# Sheet2.net
KiCad netlist of a schematic drawn in Altium Designer
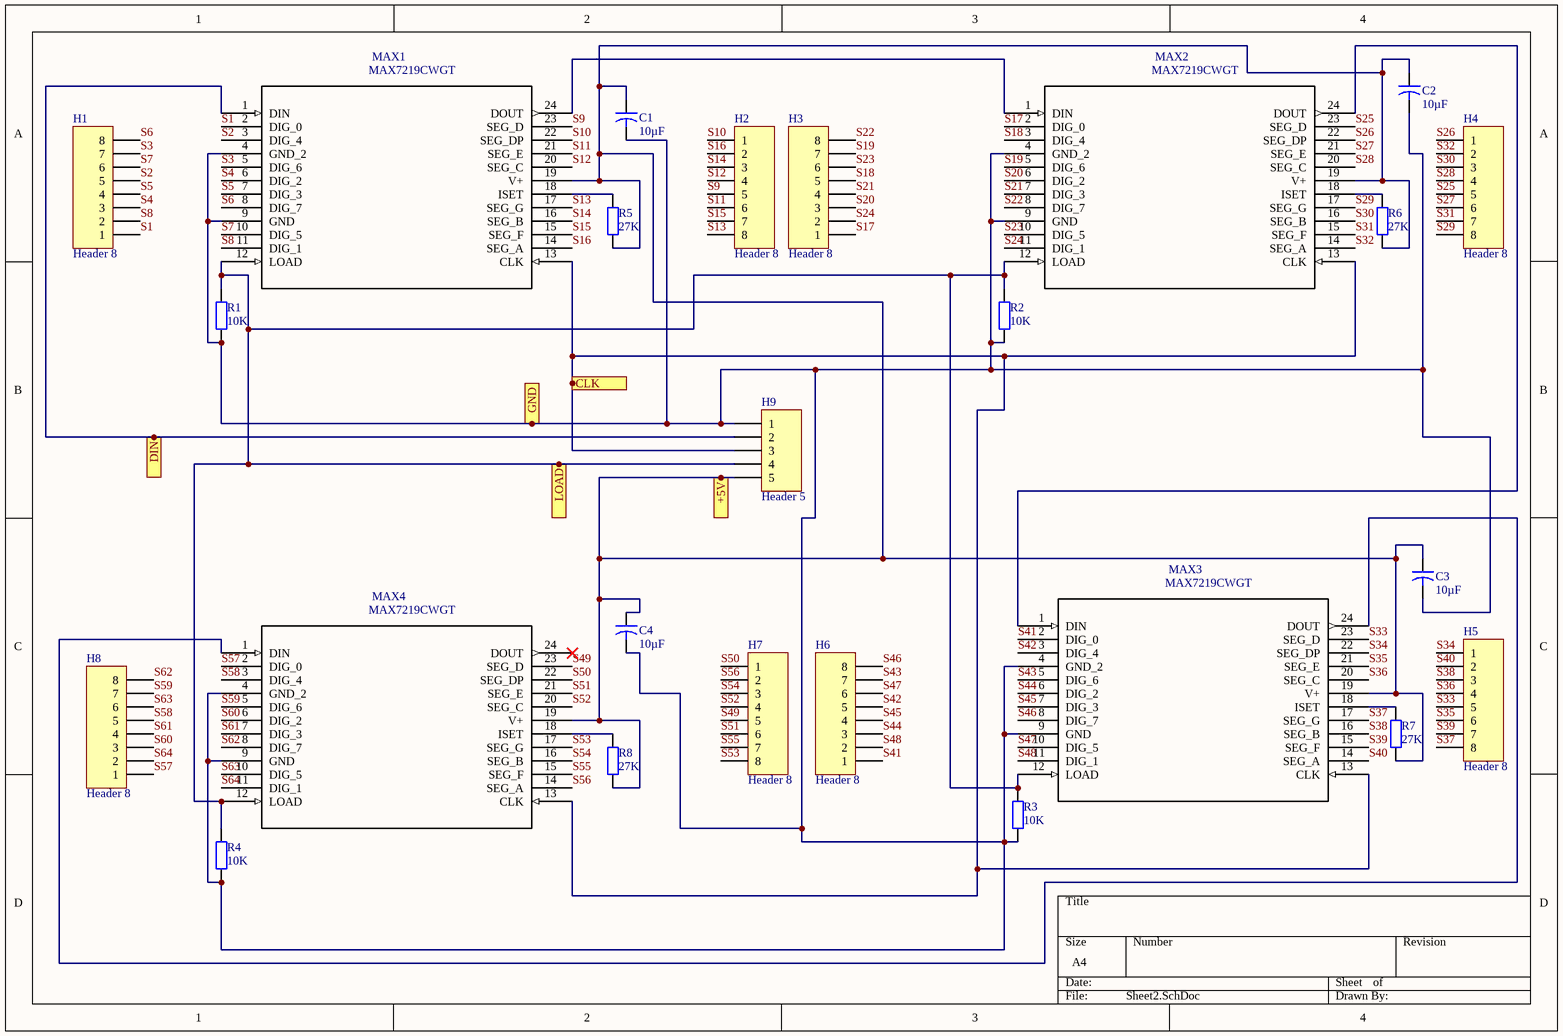
[diagram p0: Sheet2.SchDoc]

(export (version "E")
  (design (tool "Eeschema 10.0.6"))
  (components
    (comp (ref "C1")
      (value "10µF")
      (footprint "CAPR5-4X5")
      (description "Capacitor")
      (fields (field (name "Comment") "Cap2") (field (name "PUBLISHER") "Altium Limited"))
      (libsource (lib "PCB_Project_1_1") (part "Cap2"))
    )
    (comp (ref "C2")
      (value "10µF")
      (footprint "CAPR5-4X5")
      (description "Capacitor")
      (fields (field (name "Comment") "Cap2") (field (name "PUBLISHER") "Altium Limited"))
      (libsource (lib "PCB_Project_1_1") (part "Cap2"))
    )
    (comp (ref "C3")
      (value "10µF")
      (footprint "CAPR5-4X5")
      (description "Capacitor")
      (fields (field (name "Comment") "Cap2") (field (name "PUBLISHER") "Altium Limited"))
      (libsource (lib "PCB_Project_1_1") (part "Cap2"))
    )
    (comp (ref "C4")
      (value "10µF")
      (footprint "CAPR5-4X5")
      (description "Capacitor")
      (fields (field (name "Comment") "Cap2") (field (name "PUBLISHER") "Altium Limited"))
      (libsource (lib "PCB_Project_1_1") (part "Cap2"))
    )
    (comp (ref "H1")
      (value "Header 8")
      (footprint "HDR1X8")
      (description "Header, 8-Pin")
      (fields (field (name "PUBLISHER") "Altium Limited"))
      (libsource (lib "Miscellaneous Connectors") (part "Header 8"))
    )
    (comp (ref "H2")
      (value "Header 8")
      (footprint "HDR1X8")
      (description "Header, 8-Pin")
      (fields (field (name "PUBLISHER") "Altium Limited"))
      (libsource (lib "") (part "Header 8_1"))
    )
    (comp (ref "H3")
      (value "Header 8")
      (footprint "HDR1X8")
      (description "Header, 8-Pin")
      (fields (field (name "PUBLISHER") "Altium Limited"))
      (libsource (lib "Miscellaneous Connectors") (part "Header 8"))
    )
    (comp (ref "H4")
      (value "Header 8")
      (footprint "HDR1X8")
      (description "Header, 8-Pin")
      (fields (field (name "PUBLISHER") "Altium Limited"))
      (libsource (lib "") (part "Header 8_1"))
    )
    (comp (ref "H5")
      (value "Header 8")
      (footprint "HDR1X8")
      (description "Header, 8-Pin")
      (fields (field (name "PUBLISHER") "Altium Limited"))
      (libsource (lib "") (part "Header 8_1"))
    )
    (comp (ref "H6")
      (value "Header 8")
      (footprint "HDR1X8")
      (description "Header, 8-Pin")
      (fields (field (name "PUBLISHER") "Altium Limited"))
      (libsource (lib "Miscellaneous Connectors") (part "Header 8"))
    )
    (comp (ref "H7")
      (value "Header 8")
      (footprint "HDR1X8")
      (description "Header, 8-Pin")
      (fields (field (name "PUBLISHER") "Altium Limited"))
      (libsource (lib "") (part "Header 8_1"))
    )
    (comp (ref "H8")
      (value "Header 8")
      (footprint "HDR1X8")
      (description "Header, 8-Pin")
      (fields (field (name "PUBLISHER") "Altium Limited"))
      (libsource (lib "Miscellaneous Connectors") (part "Header 8"))
    )
    (comp (ref "H9")
      (value "Header 5")
      (footprint "HDR1X5")
      (description "Header, 5-Pin")
      (fields (field (name "PUBLISHER") "Altium Limited"))
      (libsource (lib "Miscellaneous Connectors") (part "Header 5"))
    )
    (comp (ref "MAX1")
      (value "MAX7219CWGT")
      (footprint "*21-0042B_24")
      (libsource (lib "MAX7219CWGT") (part "MAX7219CWGT"))
    )
    (comp (ref "MAX2")
      (value "MAX7219CWGT")
      (footprint "*21-0042B_24")
      (libsource (lib "MAX7219CWGT") (part "MAX7219CWGT"))
    )
    (comp (ref "MAX3")
      (value "MAX7219CWGT")
      (footprint "*21-0042B_24")
      (libsource (lib "MAX7219CWGT") (part "MAX7219CWGT"))
    )
    (comp (ref "MAX4")
      (value "MAX7219CWGT")
      (footprint "*21-0042B_24")
      (libsource (lib "MAX7219CWGT") (part "MAX7219CWGT"))
    )
    (comp (ref "R1")
      (value "10K")
      (footprint "AXIAL-0.4")
      (description "Resistor")
      (fields (field (name "Comment") "Res2") (field (name "PUBLISHER") "Altium Limited"))
      (libsource (lib "PCB_Project_1_1") (part "Res2_1"))
    )
    (comp (ref "R2")
      (value "10K")
      (footprint "AXIAL-0.4")
      (description "Resistor")
      (fields (field (name "Comment") "Res2") (field (name "PUBLISHER") "Altium Limited"))
      (libsource (lib "PCB_Project_1_1") (part "Res2_1"))
    )
    (comp (ref "R3")
      (value "10K")
      (footprint "AXIAL-0.4")
      (description "Resistor")
      (fields (field (name "Comment") "Res2") (field (name "PUBLISHER") "Altium Limited"))
      (libsource (lib "PCB_Project_1_1") (part "Res2_1"))
    )
    (comp (ref "R4")
      (value "10K")
      (footprint "AXIAL-0.4")
      (description "Resistor")
      (fields (field (name "Comment") "Res2") (field (name "PUBLISHER") "Altium Limited"))
      (libsource (lib "PCB_Project_1_1") (part "Res2_1"))
    )
    (comp (ref "R5")
      (value "27K")
      (footprint "AXIAL-0.4")
      (description "Resistor")
      (fields (field (name "Comment") "Res2") (field (name "PUBLISHER") "Altium Limited"))
      (libsource (lib "PCB_Project_1_1") (part "Res2"))
    )
    (comp (ref "R6")
      (value "27K")
      (footprint "AXIAL-0.4")
      (description "Resistor")
      (fields (field (name "Comment") "Res2") (field (name "PUBLISHER") "Altium Limited"))
      (libsource (lib "PCB_Project_1_1") (part "Res2"))
    )
    (comp (ref "R7")
      (value "27K")
      (footprint "AXIAL-0.4")
      (description "Resistor")
      (fields (field (name "Comment") "Res2") (field (name "PUBLISHER") "Altium Limited"))
      (libsource (lib "PCB_Project_1_1") (part "Res2"))
    )
    (comp (ref "R8")
      (value "27K")
      (footprint "AXIAL-0.4")
      (description "Resistor")
      (fields (field (name "Comment") "Res2") (field (name "PUBLISHER") "Altium Limited"))
      (libsource (lib "PCB_Project_1_1") (part "Res2"))
    )
  )
  (nets
    (net (code "1") (name "/+5V") (class "Default")
      (node (ref "C1") (pin "1") (pinfunction "1_1") (pintype "passive"))
      (node (ref "C2") (pin "1") (pinfunction "1_1") (pintype "passive"))
      (node (ref "C3") (pin "1") (pinfunction "1_1") (pintype "passive"))
      (node (ref "C4") (pin "1") (pinfunction "1_1") (pintype "passive"))
      (node (ref "H9") (pin "5") (pinfunction "5_5") (pintype "passive"))
      (node (ref "MAX1") (pin "19") (pinfunction "V+_19") (pintype "power_in"))
      (node (ref "MAX2") (pin "19") (pinfunction "V+_19") (pintype "power_in"))
      (node (ref "MAX3") (pin "19") (pinfunction "V+_19") (pintype "power_in"))
      (node (ref "MAX4") (pin "19") (pinfunction "V+_19") (pintype "power_in"))
      (node (ref "R5") (pin "1") (pinfunction "1_1") (pintype "passive"))
      (node (ref "R6") (pin "1") (pinfunction "1_1") (pintype "passive"))
      (node (ref "R7") (pin "1") (pinfunction "1_1") (pintype "passive"))
      (node (ref "R8") (pin "1") (pinfunction "1_1") (pintype "passive"))
    )
    (net (code "2") (name "/CLK") (class "Default")
      (node (ref "H9") (pin "3") (pinfunction "3_3") (pintype "passive"))
      (node (ref "MAX1") (pin "13") (pinfunction "CLK_13") (pintype "input"))
      (node (ref "MAX2") (pin "13") (pinfunction "CLK_13") (pintype "input"))
      (node (ref "MAX3") (pin "13") (pinfunction "CLK_13") (pintype "input"))
      (node (ref "MAX4") (pin "13") (pinfunction "CLK_13") (pintype "input"))
    )
    (net (code "3") (name "/DIN") (class "Default")
      (node (ref "H9") (pin "2") (pinfunction "2_2") (pintype "passive"))
      (node (ref "MAX1") (pin "1") (pinfunction "DIN_1") (pintype "input"))
    )
    (net (code "4") (name "/GND") (class "Default")
      (node (ref "C1") (pin "2") (pinfunction "2_2") (pintype "passive"))
      (node (ref "C2") (pin "2") (pinfunction "2_2") (pintype "passive"))
      (node (ref "C3") (pin "2") (pinfunction "2_2") (pintype "passive"))
      (node (ref "C4") (pin "2") (pinfunction "2_2") (pintype "passive"))
      (node (ref "H9") (pin "1") (pinfunction "1_1") (pintype "passive"))
      (node (ref "MAX1") (pin "4") (pinfunction "GND_2_4") (pintype "power_in"))
      (node (ref "MAX1") (pin "9") (pinfunction "GND_9") (pintype "power_in"))
      (node (ref "MAX2") (pin "4") (pinfunction "GND_2_4") (pintype "power_in"))
      (node (ref "MAX2") (pin "9") (pinfunction "GND_9") (pintype "power_in"))
      (node (ref "MAX3") (pin "4") (pinfunction "GND_2_4") (pintype "power_in"))
      (node (ref "MAX3") (pin "9") (pinfunction "GND_9") (pintype "power_in"))
      (node (ref "MAX4") (pin "4") (pinfunction "GND_2_4") (pintype "power_in"))
      (node (ref "MAX4") (pin "9") (pinfunction "GND_9") (pintype "power_in"))
      (node (ref "R1") (pin "1") (pinfunction "1_1") (pintype "passive"))
      (node (ref "R2") (pin "1") (pinfunction "1_1") (pintype "passive"))
      (node (ref "R3") (pin "1") (pinfunction "1_1") (pintype "passive"))
      (node (ref "R4") (pin "1") (pinfunction "1_1") (pintype "passive"))
    )
    (net (code "5") (name "/LOAD") (class "Default")
      (node (ref "H9") (pin "4") (pinfunction "4_4") (pintype "passive"))
      (node (ref "MAX1") (pin "12") (pinfunction "LOAD_12") (pintype "input"))
      (node (ref "MAX2") (pin "12") (pinfunction "LOAD_12") (pintype "input"))
      (node (ref "MAX3") (pin "12") (pinfunction "LOAD_12") (pintype "input"))
      (node (ref "MAX4") (pin "12") (pinfunction "LOAD_12") (pintype "input"))
      (node (ref "R1") (pin "2") (pinfunction "2_2") (pintype "passive"))
      (node (ref "R2") (pin "2") (pinfunction "2_2") (pintype "passive"))
      (node (ref "R3") (pin "2") (pinfunction "2_2") (pintype "passive"))
      (node (ref "R4") (pin "2") (pinfunction "2_2") (pintype "passive"))
    )
    (net (code "6") (name "/S1") (class "Default")
      (node (ref "H1") (pin "1") (pinfunction "1_1") (pintype "passive"))
      (node (ref "MAX1") (pin "2") (pinfunction "DIG_0_2") (pintype "passive"))
    )
    (net (code "7") (name "/S2") (class "Default")
      (node (ref "H1") (pin "5") (pinfunction "5_5") (pintype "passive"))
      (node (ref "MAX1") (pin "3") (pinfunction "DIG_4_3") (pintype "passive"))
    )
    (net (code "8") (name "/S3") (class "Default")
      (node (ref "H1") (pin "7") (pinfunction "7_7") (pintype "passive"))
      (node (ref "MAX1") (pin "5") (pinfunction "DIG_6_5") (pintype "passive"))
    )
    (net (code "9") (name "/S4") (class "Default")
      (node (ref "H1") (pin "3") (pinfunction "3_3") (pintype "passive"))
      (node (ref "MAX1") (pin "6") (pinfunction "DIG_2_6") (pintype "passive"))
    )
    (net (code "10") (name "/S5") (class "Default")
      (node (ref "H1") (pin "4") (pinfunction "4_4") (pintype "passive"))
      (node (ref "MAX1") (pin "7") (pinfunction "DIG_3_7") (pintype "passive"))
    )
    (net (code "11") (name "/S6") (class "Default")
      (node (ref "H1") (pin "8") (pinfunction "8_8") (pintype "passive"))
      (node (ref "MAX1") (pin "8") (pinfunction "DIG_7_8") (pintype "passive"))
    )
    (net (code "12") (name "/S7") (class "Default")
      (node (ref "H1") (pin "6") (pinfunction "6_6") (pintype "passive"))
      (node (ref "MAX1") (pin "10") (pinfunction "DIG_5_10") (pintype "passive"))
    )
    (net (code "13") (name "/S8") (class "Default")
      (node (ref "H1") (pin "2") (pinfunction "2_2") (pintype "passive"))
      (node (ref "MAX1") (pin "11") (pinfunction "DIG_1_11") (pintype "passive"))
    )
    (net (code "14") (name "/S9") (class "Default")
      (node (ref "H2") (pin "5") (pinfunction "5_5") (pintype "passive"))
      (node (ref "MAX1") (pin "23") (pinfunction "SEG_D_23") (pintype "passive"))
    )
    (net (code "15") (name "/S10") (class "Default")
      (node (ref "H2") (pin "1") (pinfunction "1_1") (pintype "passive"))
      (node (ref "MAX1") (pin "22") (pinfunction "SEG_DP_22") (pintype "passive"))
    )
    (net (code "16") (name "/S11") (class "Default")
      (node (ref "H2") (pin "6") (pinfunction "6_6") (pintype "passive"))
      (node (ref "MAX1") (pin "21") (pinfunction "SEG_E_21") (pintype "passive"))
    )
    (net (code "17") (name "/S12") (class "Default")
      (node (ref "H2") (pin "4") (pinfunction "4_4") (pintype "passive"))
      (node (ref "MAX1") (pin "20") (pinfunction "SEG_C_20") (pintype "passive"))
    )
    (net (code "18") (name "/S13") (class "Default")
      (node (ref "H2") (pin "8") (pinfunction "8_8") (pintype "passive"))
      (node (ref "MAX1") (pin "17") (pinfunction "SEG_G_17") (pintype "passive"))
    )
    (net (code "19") (name "/S14") (class "Default")
      (node (ref "H2") (pin "3") (pinfunction "3_3") (pintype "passive"))
      (node (ref "MAX1") (pin "16") (pinfunction "SEG_B_16") (pintype "passive"))
    )
    (net (code "20") (name "/S15") (class "Default")
      (node (ref "H2") (pin "7") (pinfunction "7_7") (pintype "passive"))
      (node (ref "MAX1") (pin "15") (pinfunction "SEG_F_15") (pintype "passive"))
    )
    (net (code "21") (name "/S16") (class "Default")
      (node (ref "H2") (pin "2") (pinfunction "2_2") (pintype "passive"))
      (node (ref "MAX1") (pin "14") (pinfunction "SEG_A_14") (pintype "passive"))
    )
    (net (code "22") (name "/S17") (class "Default")
      (node (ref "H3") (pin "1") (pinfunction "1_1") (pintype "passive"))
      (node (ref "MAX2") (pin "2") (pinfunction "DIG_0_2") (pintype "passive"))
    )
    (net (code "23") (name "/S18") (class "Default")
      (node (ref "H3") (pin "5") (pinfunction "5_5") (pintype "passive"))
      (node (ref "MAX2") (pin "3") (pinfunction "DIG_4_3") (pintype "passive"))
    )
    (net (code "24") (name "/S19") (class "Default")
      (node (ref "H3") (pin "7") (pinfunction "7_7") (pintype "passive"))
      (node (ref "MAX2") (pin "5") (pinfunction "DIG_6_5") (pintype "passive"))
    )
    (net (code "25") (name "/S20") (class "Default")
      (node (ref "H3") (pin "3") (pinfunction "3_3") (pintype "passive"))
      (node (ref "MAX2") (pin "6") (pinfunction "DIG_2_6") (pintype "passive"))
    )
    (net (code "26") (name "/S21") (class "Default")
      (node (ref "H3") (pin "4") (pinfunction "4_4") (pintype "passive"))
      (node (ref "MAX2") (pin "7") (pinfunction "DIG_3_7") (pintype "passive"))
    )
    (net (code "27") (name "/S22") (class "Default")
      (node (ref "H3") (pin "8") (pinfunction "8_8") (pintype "passive"))
      (node (ref "MAX2") (pin "8") (pinfunction "DIG_7_8") (pintype "passive"))
    )
    (net (code "28") (name "/S23") (class "Default")
      (node (ref "H3") (pin "6") (pinfunction "6_6") (pintype "passive"))
      (node (ref "MAX2") (pin "10") (pinfunction "DIG_5_10") (pintype "passive"))
    )
    (net (code "29") (name "/S24") (class "Default")
      (node (ref "H3") (pin "2") (pinfunction "2_2") (pintype "passive"))
      (node (ref "MAX2") (pin "11") (pinfunction "DIG_1_11") (pintype "passive"))
    )
    (net (code "30") (name "/S25") (class "Default")
      (node (ref "H4") (pin "5") (pinfunction "5_5") (pintype "passive"))
      (node (ref "MAX2") (pin "23") (pinfunction "SEG_D_23") (pintype "passive"))
    )
    (net (code "31") (name "/S26") (class "Default")
      (node (ref "H4") (pin "1") (pinfunction "1_1") (pintype "passive"))
      (node (ref "MAX2") (pin "22") (pinfunction "SEG_DP_22") (pintype "passive"))
    )
    (net (code "32") (name "/S27") (class "Default")
      (node (ref "H4") (pin "6") (pinfunction "6_6") (pintype "passive"))
      (node (ref "MAX2") (pin "21") (pinfunction "SEG_E_21") (pintype "passive"))
    )
    (net (code "33") (name "/S28") (class "Default")
      (node (ref "H4") (pin "4") (pinfunction "4_4") (pintype "passive"))
      (node (ref "MAX2") (pin "20") (pinfunction "SEG_C_20") (pintype "passive"))
    )
    (net (code "34") (name "/S29") (class "Default")
      (node (ref "H4") (pin "8") (pinfunction "8_8") (pintype "passive"))
      (node (ref "MAX2") (pin "17") (pinfunction "SEG_G_17") (pintype "passive"))
    )
    (net (code "35") (name "/S30") (class "Default")
      (node (ref "H4") (pin "3") (pinfunction "3_3") (pintype "passive"))
      (node (ref "MAX2") (pin "16") (pinfunction "SEG_B_16") (pintype "passive"))
    )
    (net (code "36") (name "/S31") (class "Default")
      (node (ref "H4") (pin "7") (pinfunction "7_7") (pintype "passive"))
      (node (ref "MAX2") (pin "15") (pinfunction "SEG_F_15") (pintype "passive"))
    )
    (net (code "37") (name "/S32") (class "Default")
      (node (ref "H4") (pin "2") (pinfunction "2_2") (pintype "passive"))
      (node (ref "MAX2") (pin "14") (pinfunction "SEG_A_14") (pintype "passive"))
    )
    (net (code "38") (name "/S33") (class "Default")
      (node (ref "H5") (pin "5") (pinfunction "5_5") (pintype "passive"))
      (node (ref "MAX3") (pin "23") (pinfunction "SEG_D_23") (pintype "passive"))
    )
    (net (code "39") (name "/S34") (class "Default")
      (node (ref "H5") (pin "1") (pinfunction "1_1") (pintype "passive"))
      (node (ref "MAX3") (pin "22") (pinfunction "SEG_DP_22") (pintype "passive"))
    )
    (net (code "40") (name "/S35") (class "Default")
      (node (ref "H5") (pin "6") (pinfunction "6_6") (pintype "passive"))
      (node (ref "MAX3") (pin "21") (pinfunction "SEG_E_21") (pintype "passive"))
    )
    (net (code "41") (name "/S36") (class "Default")
      (node (ref "H5") (pin "4") (pinfunction "4_4") (pintype "passive"))
      (node (ref "MAX3") (pin "20") (pinfunction "SEG_C_20") (pintype "passive"))
    )
    (net (code "42") (name "/S37") (class "Default")
      (node (ref "H5") (pin "8") (pinfunction "8_8") (pintype "passive"))
      (node (ref "MAX3") (pin "17") (pinfunction "SEG_G_17") (pintype "passive"))
    )
    (net (code "43") (name "/S38") (class "Default")
      (node (ref "H5") (pin "3") (pinfunction "3_3") (pintype "passive"))
      (node (ref "MAX3") (pin "16") (pinfunction "SEG_B_16") (pintype "passive"))
    )
    (net (code "44") (name "/S39") (class "Default")
      (node (ref "H5") (pin "7") (pinfunction "7_7") (pintype "passive"))
      (node (ref "MAX3") (pin "15") (pinfunction "SEG_F_15") (pintype "passive"))
    )
    (net (code "45") (name "/S40") (class "Default")
      (node (ref "H5") (pin "2") (pinfunction "2_2") (pintype "passive"))
      (node (ref "MAX3") (pin "14") (pinfunction "SEG_A_14") (pintype "passive"))
    )
    (net (code "46") (name "/S41") (class "Default")
      (node (ref "H6") (pin "1") (pinfunction "1_1") (pintype "passive"))
      (node (ref "MAX3") (pin "2") (pinfunction "DIG_0_2") (pintype "passive"))
    )
    (net (code "47") (name "/S42") (class "Default")
      (node (ref "H6") (pin "5") (pinfunction "5_5") (pintype "passive"))
      (node (ref "MAX3") (pin "3") (pinfunction "DIG_4_3") (pintype "passive"))
    )
    (net (code "48") (name "/S43") (class "Default")
      (node (ref "H6") (pin "7") (pinfunction "7_7") (pintype "passive"))
      (node (ref "MAX3") (pin "5") (pinfunction "DIG_6_5") (pintype "passive"))
    )
    (net (code "49") (name "/S44") (class "Default")
      (node (ref "H6") (pin "3") (pinfunction "3_3") (pintype "passive"))
      (node (ref "MAX3") (pin "6") (pinfunction "DIG_2_6") (pintype "passive"))
    )
    (net (code "50") (name "/S45") (class "Default")
      (node (ref "H6") (pin "4") (pinfunction "4_4") (pintype "passive"))
      (node (ref "MAX3") (pin "7") (pinfunction "DIG_3_7") (pintype "passive"))
    )
    (net (code "51") (name "/S46") (class "Default")
      (node (ref "H6") (pin "8") (pinfunction "8_8") (pintype "passive"))
      (node (ref "MAX3") (pin "8") (pinfunction "DIG_7_8") (pintype "passive"))
    )
    (net (code "52") (name "/S47") (class "Default")
      (node (ref "H6") (pin "6") (pinfunction "6_6") (pintype "passive"))
      (node (ref "MAX3") (pin "10") (pinfunction "DIG_5_10") (pintype "passive"))
    )
    (net (code "53") (name "/S48") (class "Default")
      (node (ref "H6") (pin "2") (pinfunction "2_2") (pintype "passive"))
      (node (ref "MAX3") (pin "11") (pinfunction "DIG_1_11") (pintype "passive"))
    )
    (net (code "54") (name "/S49") (class "Default")
      (node (ref "H7") (pin "5") (pinfunction "5_5") (pintype "passive"))
      (node (ref "MAX4") (pin "23") (pinfunction "SEG_D_23") (pintype "passive"))
    )
    (net (code "55") (name "/S50") (class "Default")
      (node (ref "H7") (pin "1") (pinfunction "1_1") (pintype "passive"))
      (node (ref "MAX4") (pin "22") (pinfunction "SEG_DP_22") (pintype "passive"))
    )
    (net (code "56") (name "/S51") (class "Default")
      (node (ref "H7") (pin "6") (pinfunction "6_6") (pintype "passive"))
      (node (ref "MAX4") (pin "21") (pinfunction "SEG_E_21") (pintype "passive"))
    )
    (net (code "57") (name "/S52") (class "Default")
      (node (ref "H7") (pin "4") (pinfunction "4_4") (pintype "passive"))
      (node (ref "MAX4") (pin "20") (pinfunction "SEG_C_20") (pintype "passive"))
    )
    (net (code "58") (name "/S53") (class "Default")
      (node (ref "H7") (pin "8") (pinfunction "8_8") (pintype "passive"))
      (node (ref "MAX4") (pin "17") (pinfunction "SEG_G_17") (pintype "passive"))
    )
    (net (code "59") (name "/S54") (class "Default")
      (node (ref "H7") (pin "3") (pinfunction "3_3") (pintype "passive"))
      (node (ref "MAX4") (pin "16") (pinfunction "SEG_B_16") (pintype "passive"))
    )
    (net (code "60") (name "/S55") (class "Default")
      (node (ref "H7") (pin "7") (pinfunction "7_7") (pintype "passive"))
      (node (ref "MAX4") (pin "15") (pinfunction "SEG_F_15") (pintype "passive"))
    )
    (net (code "61") (name "/S56") (class "Default")
      (node (ref "H7") (pin "2") (pinfunction "2_2") (pintype "passive"))
      (node (ref "MAX4") (pin "14") (pinfunction "SEG_A_14") (pintype "passive"))
    )
    (net (code "62") (name "/S57") (class "Default")
      (node (ref "H8") (pin "1") (pinfunction "1_1") (pintype "passive"))
      (node (ref "MAX4") (pin "2") (pinfunction "DIG_0_2") (pintype "passive"))
    )
    (net (code "63") (name "/S58") (class "Default")
      (node (ref "H8") (pin "5") (pinfunction "5_5") (pintype "passive"))
      (node (ref "MAX4") (pin "3") (pinfunction "DIG_4_3") (pintype "passive"))
    )
    (net (code "64") (name "/S59") (class "Default")
      (node (ref "H8") (pin "7") (pinfunction "7_7") (pintype "passive"))
      (node (ref "MAX4") (pin "5") (pinfunction "DIG_6_5") (pintype "passive"))
    )
    (net (code "65") (name "/S60") (class "Default")
      (node (ref "H8") (pin "3") (pinfunction "3_3") (pintype "passive"))
      (node (ref "MAX4") (pin "6") (pinfunction "DIG_2_6") (pintype "passive"))
    )
    (net (code "66") (name "/S61") (class "Default")
      (node (ref "H8") (pin "4") (pinfunction "4_4") (pintype "passive"))
      (node (ref "MAX4") (pin "7") (pinfunction "DIG_3_7") (pintype "passive"))
    )
    (net (code "67") (name "/S62") (class "Default")
      (node (ref "H8") (pin "8") (pinfunction "8_8") (pintype "passive"))
      (node (ref "MAX4") (pin "8") (pinfunction "DIG_7_8") (pintype "passive"))
    )
    (net (code "68") (name "/S63") (class "Default")
      (node (ref "H8") (pin "6") (pinfunction "6_6") (pintype "passive"))
      (node (ref "MAX4") (pin "10") (pinfunction "DIG_5_10") (pintype "passive"))
    )
    (net (code "69") (name "/S64") (class "Default")
      (node (ref "H8") (pin "2") (pinfunction "2_2") (pintype "passive"))
      (node (ref "MAX4") (pin "11") (pinfunction "DIG_1_11") (pintype "passive"))
    )
    (net (code "70") (name "Net-(MAX1-DOUT)") (class "Default")
      (node (ref "MAX1") (pin "24") (pinfunction "DOUT_24") (pintype "output"))
      (node (ref "MAX2") (pin "1") (pinfunction "DIN_1") (pintype "input"))
    )
    (net (code "71") (name "Net-(MAX1-ISET)") (class "Default")
      (node (ref "MAX1") (pin "18") (pinfunction "ISET_18") (pintype "passive"))
      (node (ref "R5") (pin "2") (pinfunction "2_2") (pintype "passive"))
    )
    (net (code "72") (name "Net-(MAX2-DOUT)") (class "Default")
      (node (ref "MAX2") (pin "24") (pinfunction "DOUT_24") (pintype "output"))
      (node (ref "MAX3") (pin "1") (pinfunction "DIN_1") (pintype "input"))
    )
    (net (code "73") (name "Net-(MAX2-ISET)") (class "Default")
      (node (ref "MAX2") (pin "18") (pinfunction "ISET_18") (pintype "passive"))
      (node (ref "R6") (pin "2") (pinfunction "2_2") (pintype "passive"))
    )
    (net (code "74") (name "Net-(MAX3-DOUT)") (class "Default")
      (node (ref "MAX3") (pin "24") (pinfunction "DOUT_24") (pintype "output"))
      (node (ref "MAX4") (pin "1") (pinfunction "DIN_1") (pintype "input"))
    )
    (net (code "75") (name "Net-(MAX3-ISET)") (class "Default")
      (node (ref "MAX3") (pin "18") (pinfunction "ISET_18") (pintype "passive"))
      (node (ref "R7") (pin "2") (pinfunction "2_2") (pintype "passive"))
    )
    (net (code "76") (name "Net-(MAX4-ISET)") (class "Default")
      (node (ref "MAX4") (pin "18") (pinfunction "ISET_18") (pintype "passive"))
      (node (ref "R8") (pin "2") (pinfunction "2_2") (pintype "passive"))
    )
    (net (code "77") (name "unconnected-(MAX4-DOUT-Pad24)") (class "Default")
      (node (ref "MAX4") (pin "24") (pinfunction "DOUT_24") (pintype "output+no_connect"))
    )
  )
)
